# Main.net
KiCad netlist of a schematic drawn in Altium Designer
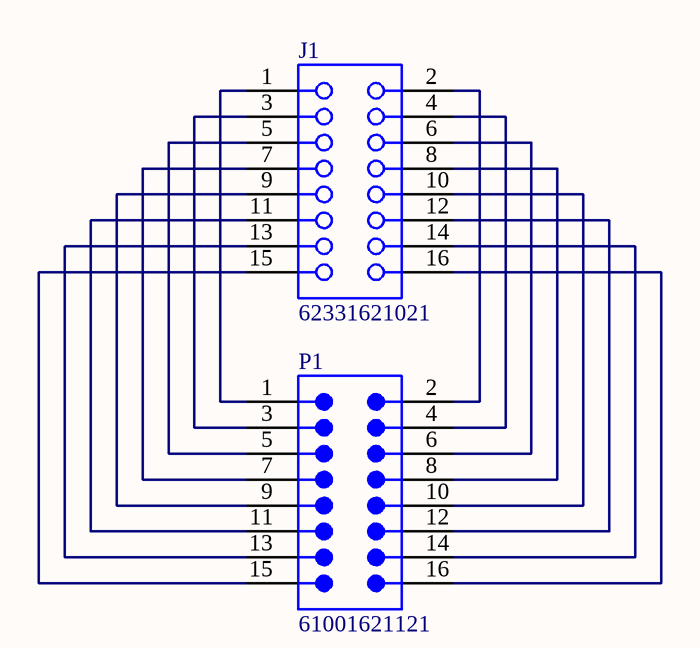
[diagram p0: Main.SchDoc]

(export (version "E")
  (design (tool "Eeschema 10.0.6"))
  (components
    (comp (ref "J1")
      (value "62331621021")
      (footprint "62301621021")
      (description "SMT Vertical Socket Header WR-PHD, Pitch 1.27 mm, Dual Row, 16 pins")
      (libsource (lib "Altium Content Vault") (part "Header_Female_2R_16P"))
    )
    (comp (ref "P1")
      (value "61001621121")
      (footprint "61001621121")
      (description "SMT Vertical Pin Header WR-PHD, Pitch 2.54 mm, Dual Row, 16 pins")
      (libsource (lib "Altium Content Vault") (part "Header_Male_2R_16P"))
    )
  )
  (nets
    (net (code "1") (name "Net-(J1-Pad1)") (class "Default")
      (node (ref "J1") (pin "1") (pinfunction "1_1") (pintype "passive"))
      (node (ref "P1") (pin "1") (pinfunction "1_1") (pintype "passive"))
    )
    (net (code "2") (name "Net-(J1-Pad2)") (class "Default")
      (node (ref "J1") (pin "2") (pinfunction "2_2") (pintype "passive"))
      (node (ref "P1") (pin "2") (pinfunction "2_2") (pintype "passive"))
    )
    (net (code "3") (name "Net-(J1-Pad3)") (class "Default")
      (node (ref "J1") (pin "3") (pinfunction "3_3") (pintype "passive"))
      (node (ref "P1") (pin "3") (pinfunction "3_3") (pintype "passive"))
    )
    (net (code "4") (name "Net-(J1-Pad4)") (class "Default")
      (node (ref "J1") (pin "4") (pinfunction "4_4") (pintype "passive"))
      (node (ref "P1") (pin "4") (pinfunction "4_4") (pintype "passive"))
    )
    (net (code "5") (name "Net-(J1-Pad5)") (class "Default")
      (node (ref "J1") (pin "5") (pinfunction "5_5") (pintype "passive"))
      (node (ref "P1") (pin "5") (pinfunction "5_5") (pintype "passive"))
    )
    (net (code "6") (name "Net-(J1-Pad6)") (class "Default")
      (node (ref "J1") (pin "6") (pinfunction "6_6") (pintype "passive"))
      (node (ref "P1") (pin "6") (pinfunction "6_6") (pintype "passive"))
    )
    (net (code "7") (name "Net-(J1-Pad7)") (class "Default")
      (node (ref "J1") (pin "7") (pinfunction "7_7") (pintype "passive"))
      (node (ref "P1") (pin "7") (pinfunction "7_7") (pintype "passive"))
    )
    (net (code "8") (name "Net-(J1-Pad8)") (class "Default")
      (node (ref "J1") (pin "8") (pinfunction "8_8") (pintype "passive"))
      (node (ref "P1") (pin "8") (pinfunction "8_8") (pintype "passive"))
    )
    (net (code "9") (name "Net-(J1-Pad9)") (class "Default")
      (node (ref "J1") (pin "9") (pinfunction "9_9") (pintype "passive"))
      (node (ref "P1") (pin "9") (pinfunction "9_9") (pintype "passive"))
    )
    (net (code "10") (name "Net-(J1-Pad10)") (class "Default")
      (node (ref "J1") (pin "10") (pinfunction "10_10") (pintype "passive"))
      (node (ref "P1") (pin "10") (pinfunction "10_10") (pintype "passive"))
    )
    (net (code "11") (name "Net-(J1-Pad11)") (class "Default")
      (node (ref "J1") (pin "11") (pinfunction "11_11") (pintype "passive"))
      (node (ref "P1") (pin "11") (pinfunction "11_11") (pintype "passive"))
    )
    (net (code "12") (name "Net-(J1-Pad12)") (class "Default")
      (node (ref "J1") (pin "12") (pinfunction "12_12") (pintype "passive"))
      (node (ref "P1") (pin "12") (pinfunction "12_12") (pintype "passive"))
    )
    (net (code "13") (name "Net-(J1-Pad13)") (class "Default")
      (node (ref "J1") (pin "13") (pinfunction "13_13") (pintype "passive"))
      (node (ref "P1") (pin "13") (pinfunction "13_13") (pintype "passive"))
    )
    (net (code "14") (name "Net-(J1-Pad14)") (class "Default")
      (node (ref "J1") (pin "14") (pinfunction "14_14") (pintype "passive"))
      (node (ref "P1") (pin "14") (pinfunction "14_14") (pintype "passive"))
    )
    (net (code "15") (name "Net-(J1-Pad15)") (class "Default")
      (node (ref "J1") (pin "15") (pinfunction "15_15") (pintype "passive"))
      (node (ref "P1") (pin "15") (pinfunction "15_15") (pintype "passive"))
    )
    (net (code "16") (name "Net-(J1-Pad16)") (class "Default")
      (node (ref "J1") (pin "16") (pinfunction "16_16") (pintype "passive"))
      (node (ref "P1") (pin "16") (pinfunction "16_16") (pintype "passive"))
    )
  )
)
